# TestAirPollutionFinal.net
KiCad netlist of a schematic drawn in EAGLE
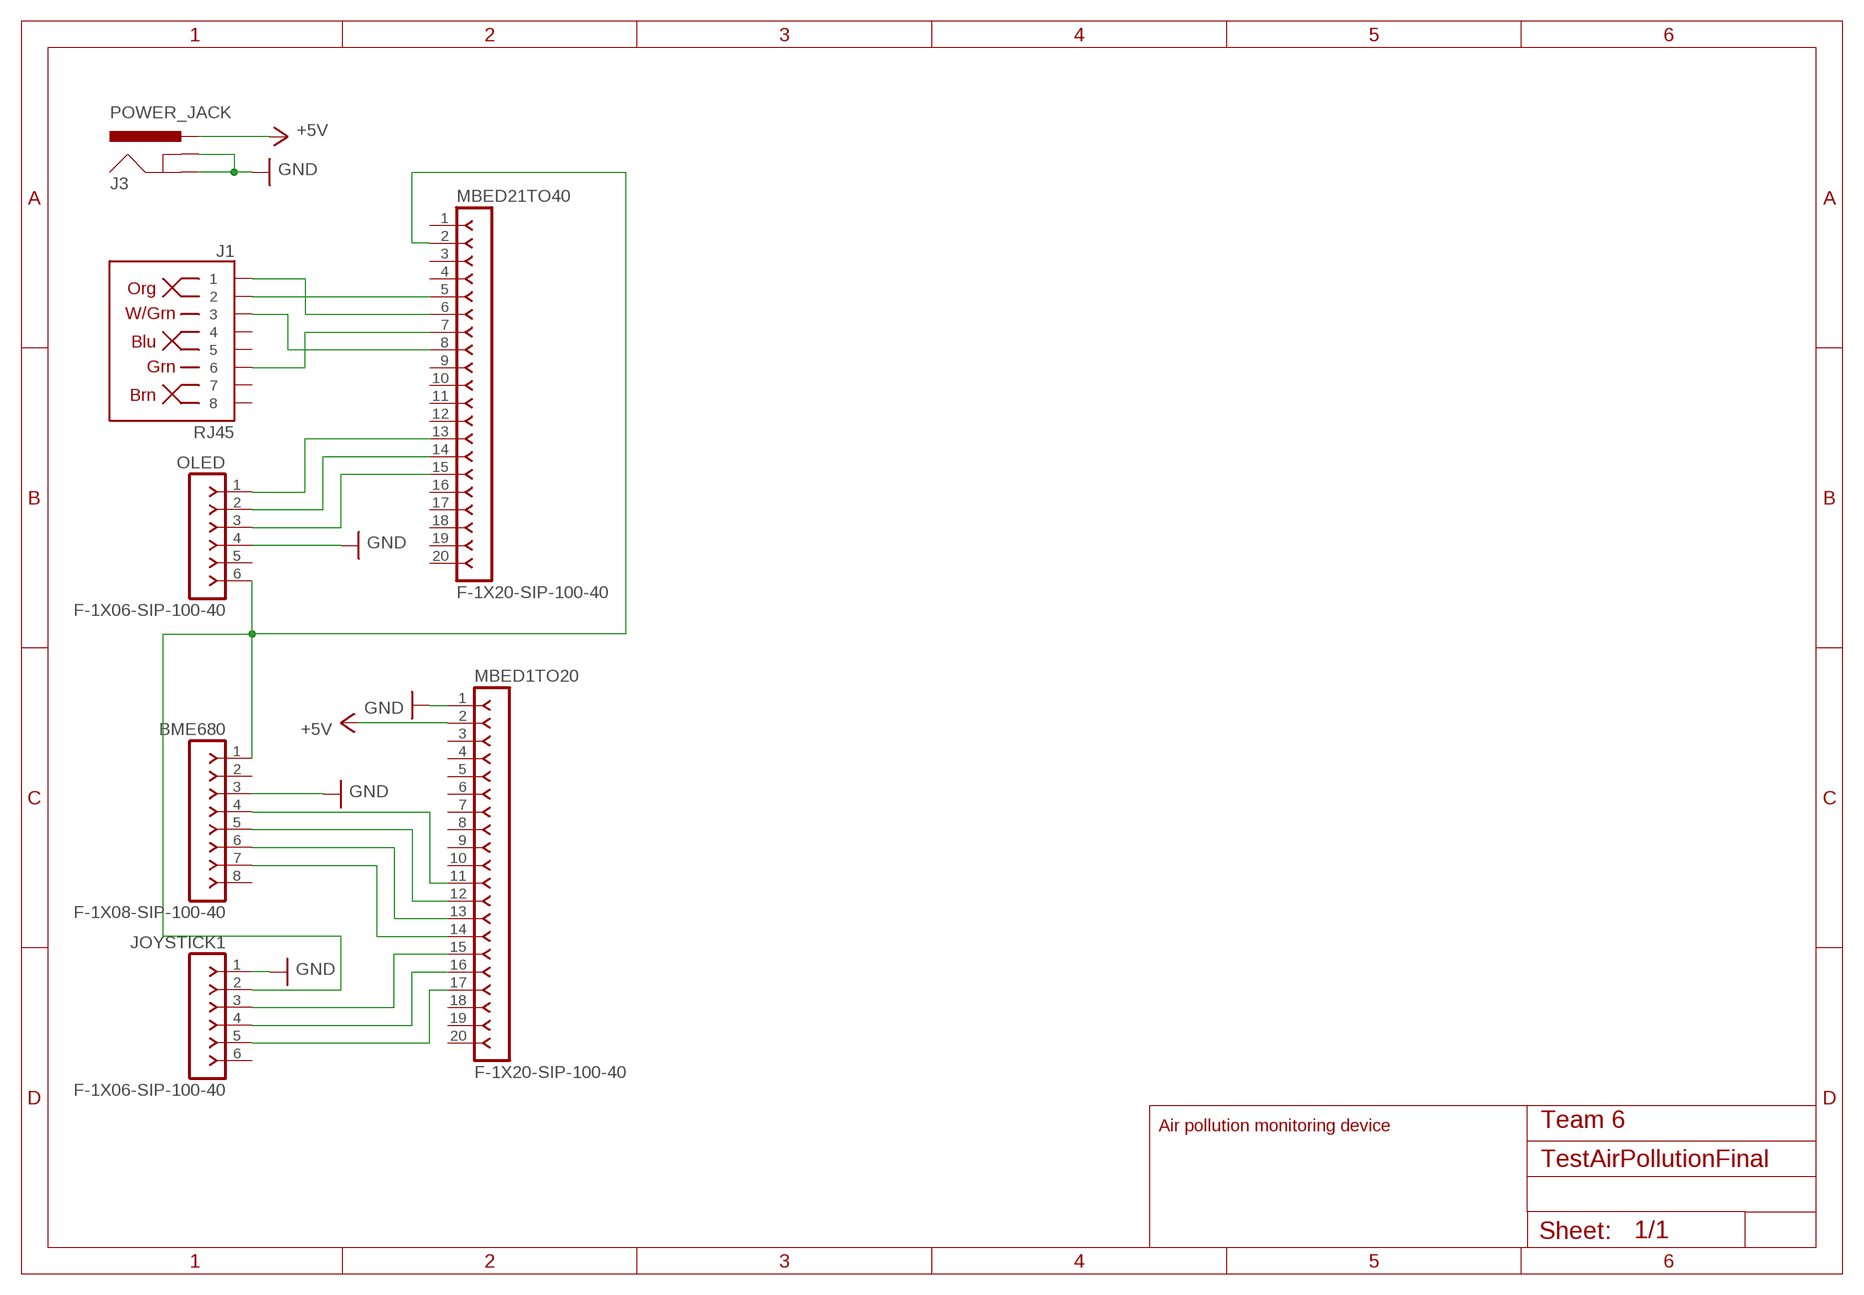
[diagram p0: schematic, sheet 1]

(export (version "E")
  (design (tool "Eeschema 10.0.6"))
  (components
    (comp (ref "BME680")
      (value "F-1X08-SIP-100-40")
      (footprint "eagle-import:SIP-100-08-40")
      (libsource (lib "eagle-import") (part "F-1X08-SIP-100-40"))
    )
    (comp (ref "J1")
      (value "RJ45")
      (footprint "eagle-import:RJ45-8")
      (libsource (lib "eagle-import") (part "RJ45-8"))
    )
    (comp (ref "J3")
      (value "POWER_JACK")
      (footprint "eagle-import:POWER_JACK_PTH")
      (libsource (lib "eagle-import") (part "POWER_JACK"))
    )
    (comp (ref "JOYSTICK1")
      (value "F-1X06-SIP-100-40")
      (footprint "eagle-import:SIP-100-06-40")
      (libsource (lib "eagle-import") (part "F-1X06-SIP-100-40"))
    )
    (comp (ref "MBED1TO20")
      (value "F-1X20-SIP-100-40")
      (footprint "eagle-import:SIP-100-20-40")
      (libsource (lib "eagle-import") (part "F-1X20-SIP-100-40"))
    )
    (comp (ref "MBED21TO40")
      (value "F-1X20-SIP-100-40")
      (footprint "eagle-import:SIP-100-20-40")
      (libsource (lib "eagle-import") (part "F-1X20-SIP-100-40"))
    )
    (comp (ref "OLED")
      (value "F-1X06-SIP-100-40")
      (footprint "eagle-import:SIP-100-06-40")
      (libsource (lib "eagle-import") (part "F-1X06-SIP-100-40"))
    )
  )
  (nets
    (net (code "1") (name "+5V") (class "Default")
      (node (ref "J3") (pin "PWR") (pinfunction "PWR_PWR") (pintype "bidirectional"))
      (node (ref "MBED1TO20") (pin "2") (pinfunction "2_2") (pintype "passive"))
    )
    (net (code "2") (name "GND") (class "Default")
      (node (ref "BME680") (pin "3") (pinfunction "3_3") (pintype "passive"))
      (node (ref "J3") (pin "GND") (pinfunction "GND_GND") (pintype "bidirectional"))
      (node (ref "J3") (pin "GNDBREAK") (pinfunction "GNDBREAK_GNDBREAK") (pintype "bidirectional"))
      (node (ref "JOYSTICK1") (pin "1") (pinfunction "1_1") (pintype "passive"))
      (node (ref "MBED1TO20") (pin "1") (pinfunction "1_1") (pintype "passive"))
      (node (ref "OLED") (pin "4") (pinfunction "4_4") (pintype "passive"))
    )
    (net (code "3") (name "Net-(BME680-Pad1)") (class "Default")
      (node (ref "BME680") (pin "1") (pinfunction "1_1") (pintype "passive"))
      (node (ref "JOYSTICK1") (pin "2") (pinfunction "2_2") (pintype "passive"))
      (node (ref "MBED21TO40") (pin "2") (pinfunction "2_2") (pintype "passive"))
      (node (ref "OLED") (pin "6") (pinfunction "6_6") (pintype "passive"))
    )
    (net (code "4") (name "Net-(BME680-Pad4)") (class "Default")
      (node (ref "BME680") (pin "4") (pinfunction "4_4") (pintype "passive"))
      (node (ref "MBED1TO20") (pin "11") (pinfunction "11_11") (pintype "passive"))
    )
    (net (code "5") (name "Net-(BME680-Pad5)") (class "Default")
      (node (ref "BME680") (pin "5") (pinfunction "5_5") (pintype "passive"))
      (node (ref "MBED1TO20") (pin "12") (pinfunction "12_12") (pintype "passive"))
    )
    (net (code "6") (name "Net-(BME680-Pad6)") (class "Default")
      (node (ref "BME680") (pin "6") (pinfunction "6_6") (pintype "passive"))
      (node (ref "MBED1TO20") (pin "13") (pinfunction "13_13") (pintype "passive"))
    )
    (net (code "7") (name "Net-(BME680-Pad7)") (class "Default")
      (node (ref "BME680") (pin "7") (pinfunction "7_7") (pintype "passive"))
      (node (ref "MBED1TO20") (pin "14") (pinfunction "14_14") (pintype "passive"))
    )
    (net (code "8") (name "Net-(J1-Pad1)") (class "Default")
      (node (ref "J1") (pin "1") (pinfunction "1_1") (pintype "bidirectional"))
      (node (ref "MBED21TO40") (pin "6") (pinfunction "6_6") (pintype "passive"))
    )
    (net (code "9") (name "Net-(J1-Pad2)") (class "Default")
      (node (ref "J1") (pin "2") (pinfunction "2_2") (pintype "bidirectional"))
      (node (ref "MBED21TO40") (pin "5") (pinfunction "5_5") (pintype "passive"))
    )
    (net (code "10") (name "Net-(J1-Pad3)") (class "Default")
      (node (ref "J1") (pin "3") (pinfunction "3_3") (pintype "bidirectional"))
      (node (ref "MBED21TO40") (pin "8") (pinfunction "8_8") (pintype "passive"))
    )
    (net (code "11") (name "Net-(J1-Pad6)") (class "Default")
      (node (ref "J1") (pin "6") (pinfunction "6_6") (pintype "bidirectional"))
      (node (ref "MBED21TO40") (pin "7") (pinfunction "7_7") (pintype "passive"))
    )
    (net (code "12") (name "Net-(JOYSTICK1-Pad3)") (class "Default")
      (node (ref "JOYSTICK1") (pin "3") (pinfunction "3_3") (pintype "passive"))
      (node (ref "MBED1TO20") (pin "15") (pinfunction "15_15") (pintype "passive"))
    )
    (net (code "13") (name "Net-(JOYSTICK1-Pad4)") (class "Default")
      (node (ref "JOYSTICK1") (pin "4") (pinfunction "4_4") (pintype "passive"))
      (node (ref "MBED1TO20") (pin "16") (pinfunction "16_16") (pintype "passive"))
    )
    (net (code "14") (name "Net-(JOYSTICK1-Pad5)") (class "Default")
      (node (ref "JOYSTICK1") (pin "5") (pinfunction "5_5") (pintype "passive"))
      (node (ref "MBED1TO20") (pin "17") (pinfunction "17_17") (pintype "passive"))
    )
    (net (code "15") (name "Net-(MBED21TO40-Pad13)") (class "Default")
      (node (ref "MBED21TO40") (pin "13") (pinfunction "13_13") (pintype "passive"))
      (node (ref "OLED") (pin "1") (pinfunction "1_1") (pintype "passive"))
    )
    (net (code "16") (name "Net-(MBED21TO40-Pad14)") (class "Default")
      (node (ref "MBED21TO40") (pin "14") (pinfunction "14_14") (pintype "passive"))
      (node (ref "OLED") (pin "2") (pinfunction "2_2") (pintype "passive"))
    )
    (net (code "17") (name "Net-(MBED21TO40-Pad15)") (class "Default")
      (node (ref "MBED21TO40") (pin "15") (pinfunction "15_15") (pintype "passive"))
      (node (ref "OLED") (pin "3") (pinfunction "3_3") (pintype "passive"))
    )
    (net (code "18") (name "unconnected-(BME680-Pad2)") (class "Default")
      (node (ref "BME680") (pin "2") (pinfunction "2_2") (pintype "passive"))
    )
    (net (code "19") (name "unconnected-(BME680-Pad8)") (class "Default")
      (node (ref "BME680") (pin "8") (pinfunction "8_8") (pintype "passive"))
    )
    (net (code "20") (name "unconnected-(J1-Pad4)") (class "Default")
      (node (ref "J1") (pin "4") (pinfunction "4_4") (pintype "bidirectional"))
    )
    (net (code "21") (name "unconnected-(J1-Pad5)") (class "Default")
      (node (ref "J1") (pin "5") (pinfunction "5_5") (pintype "bidirectional"))
    )
    (net (code "22") (name "unconnected-(J1-Pad7)") (class "Default")
      (node (ref "J1") (pin "7") (pinfunction "7_7") (pintype "bidirectional"))
    )
    (net (code "23") (name "unconnected-(J1-Pad8)") (class "Default")
      (node (ref "J1") (pin "8") (pinfunction "8_8") (pintype "bidirectional"))
    )
    (net (code "24") (name "unconnected-(JOYSTICK1-Pad6)") (class "Default")
      (node (ref "JOYSTICK1") (pin "6") (pinfunction "6_6") (pintype "passive"))
    )
    (net (code "25") (name "unconnected-(MBED1TO20-Pad3)") (class "Default")
      (node (ref "MBED1TO20") (pin "3") (pinfunction "3_3") (pintype "passive"))
    )
    (net (code "26") (name "unconnected-(MBED1TO20-Pad4)") (class "Default")
      (node (ref "MBED1TO20") (pin "4") (pinfunction "4_4") (pintype "passive"))
    )
    (net (code "27") (name "unconnected-(MBED1TO20-Pad5)") (class "Default")
      (node (ref "MBED1TO20") (pin "5") (pinfunction "5_5") (pintype "passive"))
    )
    (net (code "28") (name "unconnected-(MBED1TO20-Pad6)") (class "Default")
      (node (ref "MBED1TO20") (pin "6") (pinfunction "6_6") (pintype "passive"))
    )
    (net (code "29") (name "unconnected-(MBED1TO20-Pad7)") (class "Default")
      (node (ref "MBED1TO20") (pin "7") (pinfunction "7_7") (pintype "passive"))
    )
    (net (code "30") (name "unconnected-(MBED1TO20-Pad8)") (class "Default")
      (node (ref "MBED1TO20") (pin "8") (pinfunction "8_8") (pintype "passive"))
    )
    (net (code "31") (name "unconnected-(MBED1TO20-Pad9)") (class "Default")
      (node (ref "MBED1TO20") (pin "9") (pinfunction "9_9") (pintype "passive"))
    )
    (net (code "32") (name "unconnected-(MBED1TO20-Pad10)") (class "Default")
      (node (ref "MBED1TO20") (pin "10") (pinfunction "10_10") (pintype "passive"))
    )
    (net (code "33") (name "unconnected-(MBED1TO20-Pad18)") (class "Default")
      (node (ref "MBED1TO20") (pin "18") (pinfunction "18_18") (pintype "passive"))
    )
    (net (code "34") (name "unconnected-(MBED1TO20-Pad19)") (class "Default")
      (node (ref "MBED1TO20") (pin "19") (pinfunction "19_19") (pintype "passive"))
    )
    (net (code "35") (name "unconnected-(MBED1TO20-Pad20)") (class "Default")
      (node (ref "MBED1TO20") (pin "20") (pinfunction "20_20") (pintype "passive"))
    )
    (net (code "36") (name "unconnected-(MBED21TO40-Pad1)") (class "Default")
      (node (ref "MBED21TO40") (pin "1") (pinfunction "1_1") (pintype "passive"))
    )
    (net (code "37") (name "unconnected-(MBED21TO40-Pad3)") (class "Default")
      (node (ref "MBED21TO40") (pin "3") (pinfunction "3_3") (pintype "passive"))
    )
    (net (code "38") (name "unconnected-(MBED21TO40-Pad4)") (class "Default")
      (node (ref "MBED21TO40") (pin "4") (pinfunction "4_4") (pintype "passive"))
    )
    (net (code "39") (name "unconnected-(MBED21TO40-Pad9)") (class "Default")
      (node (ref "MBED21TO40") (pin "9") (pinfunction "9_9") (pintype "passive"))
    )
    (net (code "40") (name "unconnected-(MBED21TO40-Pad10)") (class "Default")
      (node (ref "MBED21TO40") (pin "10") (pinfunction "10_10") (pintype "passive"))
    )
    (net (code "41") (name "unconnected-(MBED21TO40-Pad11)") (class "Default")
      (node (ref "MBED21TO40") (pin "11") (pinfunction "11_11") (pintype "passive"))
    )
    (net (code "42") (name "unconnected-(MBED21TO40-Pad12)") (class "Default")
      (node (ref "MBED21TO40") (pin "12") (pinfunction "12_12") (pintype "passive"))
    )
    (net (code "43") (name "unconnected-(MBED21TO40-Pad16)") (class "Default")
      (node (ref "MBED21TO40") (pin "16") (pinfunction "16_16") (pintype "passive"))
    )
    (net (code "44") (name "unconnected-(MBED21TO40-Pad17)") (class "Default")
      (node (ref "MBED21TO40") (pin "17") (pinfunction "17_17") (pintype "passive"))
    )
    (net (code "45") (name "unconnected-(MBED21TO40-Pad18)") (class "Default")
      (node (ref "MBED21TO40") (pin "18") (pinfunction "18_18") (pintype "passive"))
    )
    (net (code "46") (name "unconnected-(MBED21TO40-Pad19)") (class "Default")
      (node (ref "MBED21TO40") (pin "19") (pinfunction "19_19") (pintype "passive"))
    )
    (net (code "47") (name "unconnected-(MBED21TO40-Pad20)") (class "Default")
      (node (ref "MBED21TO40") (pin "20") (pinfunction "20_20") (pintype "passive"))
    )
    (net (code "48") (name "unconnected-(OLED-Pad5)") (class "Default")
      (node (ref "OLED") (pin "5") (pinfunction "5_5") (pintype "passive"))
    )
  )
)
